# sensor_module_temp_pulse_light_v1.net
KiCad netlist of a schematic drawn in EAGLE
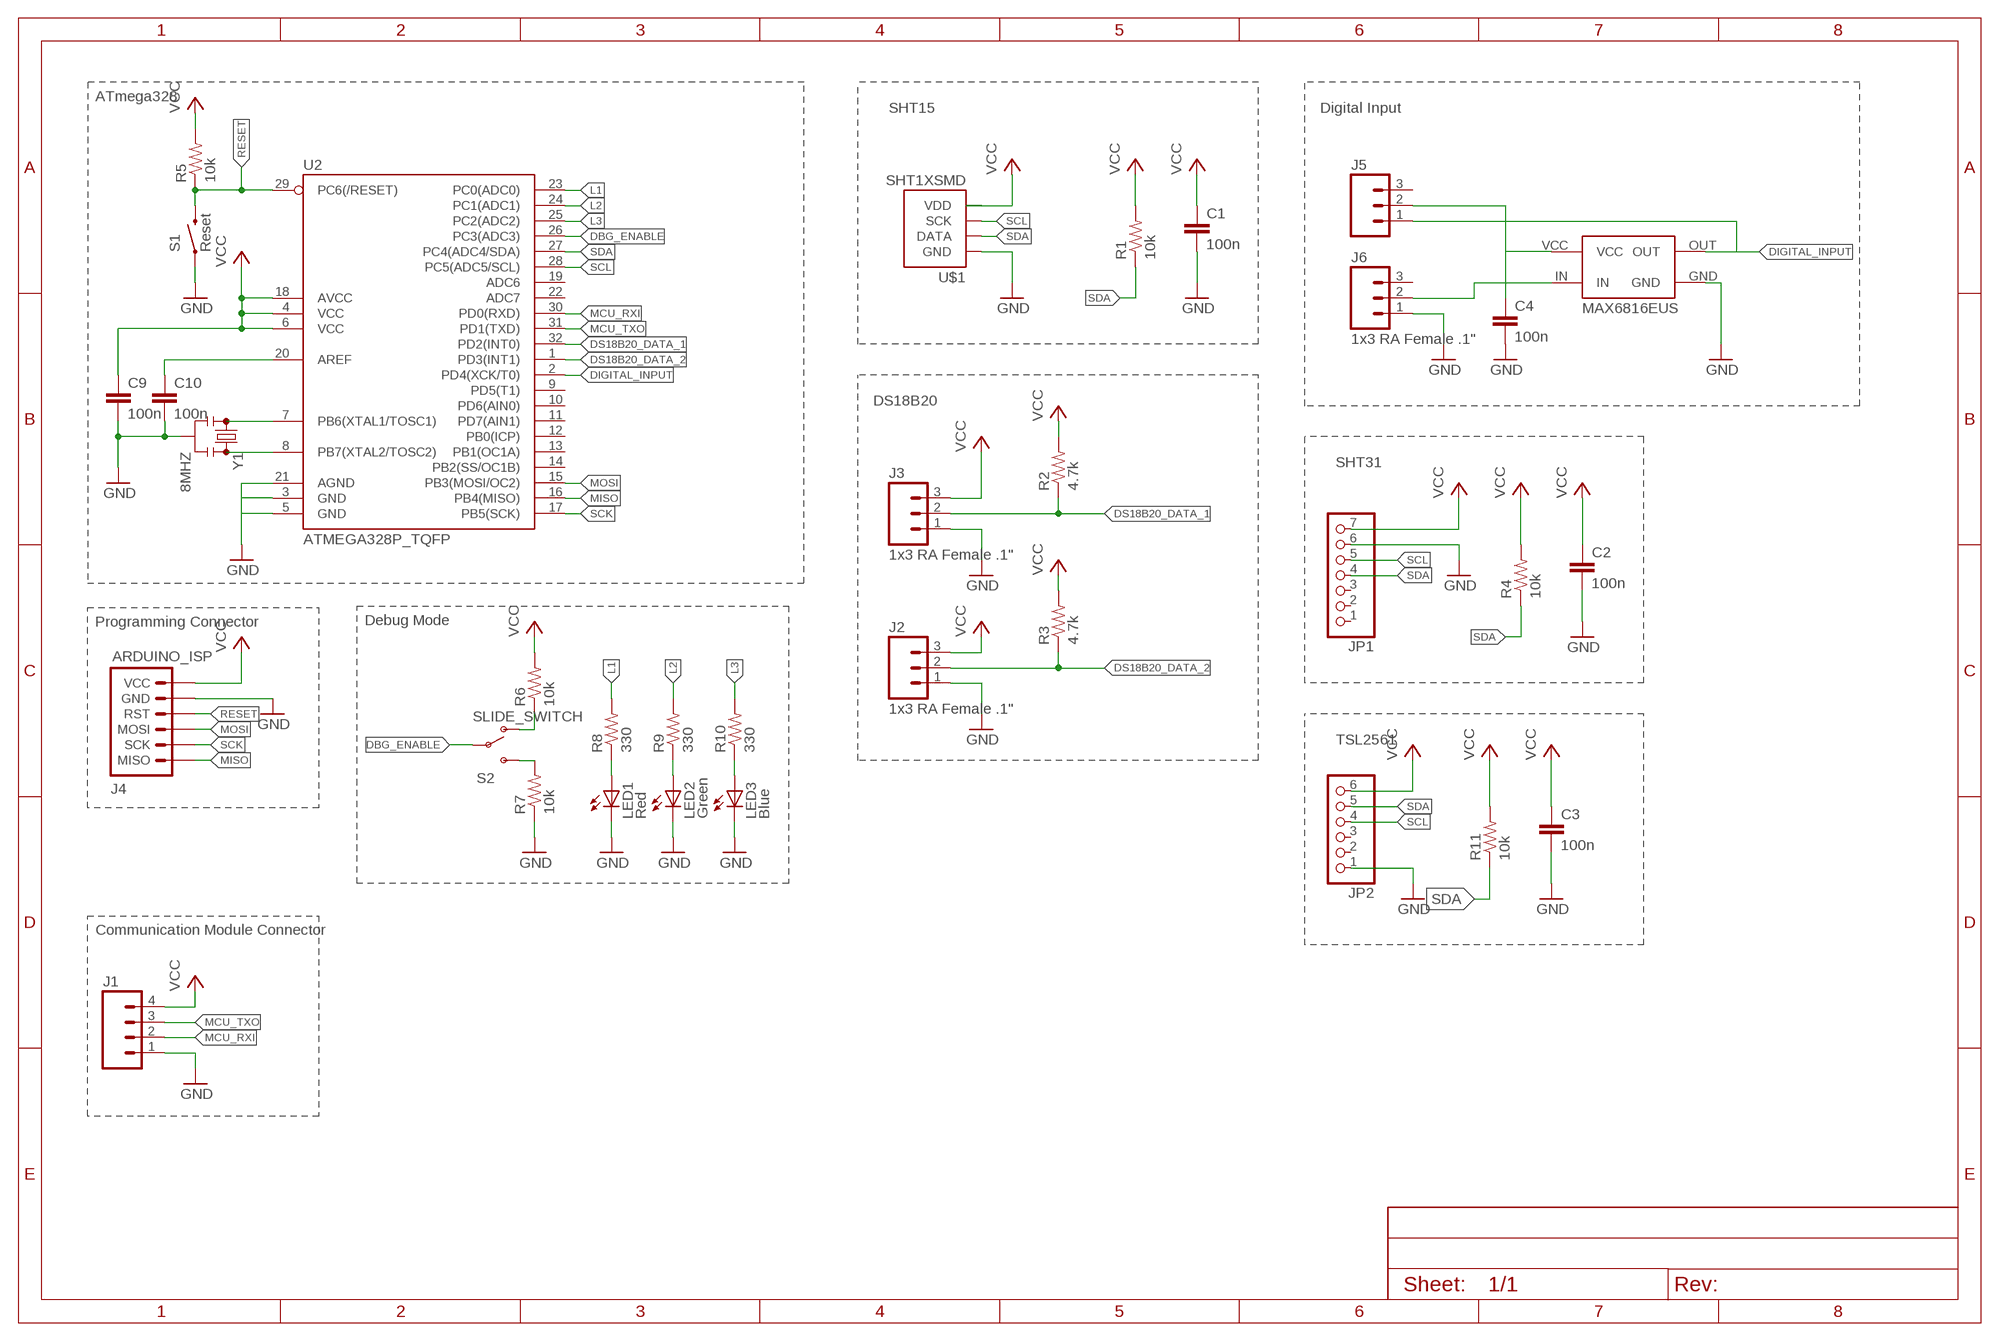
[diagram p0: schematic, sheet 1]

(export (version "E")
  (design (tool "Eeschema 10.0.6"))
  (components
    (comp (ref "C1")
      (value "100n")
      (footprint "eagle-import:C0805")
      (libsource (lib "eagle-import") (part "C"))
    )
    (comp (ref "C2")
      (value "100n")
      (footprint "eagle-import:C0805")
      (libsource (lib "eagle-import") (part "C"))
    )
    (comp (ref "C3")
      (value "100n")
      (footprint "eagle-import:C0805")
      (libsource (lib "eagle-import") (part "C"))
    )
    (comp (ref "C4")
      (value "100n")
      (footprint "eagle-import:C0805")
      (libsource (lib "eagle-import") (part "C"))
    )
    (comp (ref "C9")
      (value "100n")
      (footprint "eagle-import:C0805")
      (libsource (lib "eagle-import") (part "C"))
    )
    (comp (ref "C10")
      (value "100n")
      (footprint "eagle-import:C0805")
      (libsource (lib "eagle-import") (part "C"))
    )
    (comp (ref "J1")
      (value "M041X04_NO_SILK")
      (footprint "eagle-import:1X04_NO_SILK")
      (libsource (lib "eagle-import") (part "M041X04_NO_SILK"))
    )
    (comp (ref "J2")
      (value "1x3 RA Female .1\"")
      (footprint "eagle-import:1X03_SMD_RA_FEMALE")
      (libsource (lib "eagle-import") (part "M03SMD_RA_FEMALE"))
    )
    (comp (ref "J3")
      (value "1x3 RA Female .1\"")
      (footprint "eagle-import:1X03_SMD_RA_FEMALE")
      (libsource (lib "eagle-import") (part "M03SMD_RA_FEMALE"))
    )
    (comp (ref "J4")
      (value "ARDUINO_ISP")
      (footprint "eagle-import:M-2X3")
      (libsource (lib "eagle-import") (part "ARDUINO_ISP"))
    )
    (comp (ref "J5")
      (value "M031X03_NO_SILK")
      (footprint "eagle-import:1X03_NO_SILK")
      (libsource (lib "eagle-import") (part "M031X03_NO_SILK"))
    )
    (comp (ref "J6")
      (value "1x3 RA Female .1\"")
      (footprint "eagle-import:1X03_SMD_RA_FEMALE")
      (libsource (lib "eagle-import") (part "M03SMD_RA_FEMALE"))
    )
    (comp (ref "JP1")
      (value "PINHD-1X7")
      (footprint "eagle-import:1X07")
      (libsource (lib "eagle-import") (part "PINHD-1X7"))
    )
    (comp (ref "JP2")
      (value "PINHD-1X6")
      (footprint "eagle-import:1X06")
      (libsource (lib "eagle-import") (part "PINHD-1X6"))
    )
    (comp (ref "LED1")
      (value "Red")
      (footprint "eagle-import:SML0805")
      (libsource (lib "eagle-import") (part "LEDSML0805"))
    )
    (comp (ref "LED2")
      (value "Green")
      (footprint "eagle-import:SML0805")
      (libsource (lib "eagle-import") (part "LEDSML0805"))
    )
    (comp (ref "LED3")
      (value "Blue")
      (footprint "eagle-import:SML0805")
      (libsource (lib "eagle-import") (part "LEDSML0805"))
    )
    (comp (ref "R1")
      (value "10k")
      (footprint "eagle-import:0805")
      (libsource (lib "eagle-import") (part "RESISTOR0805-RES"))
    )
    (comp (ref "R2")
      (value "4.7k")
      (footprint "eagle-import:0805")
      (libsource (lib "eagle-import") (part "RESISTOR0805-RES"))
    )
    (comp (ref "R3")
      (value "4.7k")
      (footprint "eagle-import:0805")
      (libsource (lib "eagle-import") (part "RESISTOR0805-RES"))
    )
    (comp (ref "R4")
      (value "10k")
      (footprint "eagle-import:0805")
      (libsource (lib "eagle-import") (part "RESISTOR0805-RES"))
    )
    (comp (ref "R5")
      (value "10k")
      (footprint "eagle-import:0805")
      (libsource (lib "eagle-import") (part "RESISTOR0805-RES"))
    )
    (comp (ref "R6")
      (value "10k")
      (footprint "eagle-import:0805")
      (libsource (lib "eagle-import") (part "RESISTOR0805-RES"))
    )
    (comp (ref "R7")
      (value "10k")
      (footprint "eagle-import:0805")
      (libsource (lib "eagle-import") (part "RESISTOR0805-RES"))
    )
    (comp (ref "R8")
      (value "330")
      (footprint "eagle-import:0805")
      (libsource (lib "eagle-import") (part "RESISTOR0805-RES"))
    )
    (comp (ref "R9")
      (value "330")
      (footprint "eagle-import:0805")
      (libsource (lib "eagle-import") (part "RESISTOR0805-RES"))
    )
    (comp (ref "R10")
      (value "330")
      (footprint "eagle-import:0805")
      (libsource (lib "eagle-import") (part "RESISTOR0805-RES"))
    )
    (comp (ref "R11")
      (value "10k")
      (footprint "eagle-import:0805")
      (libsource (lib "eagle-import") (part "RESISTOR0805-RES"))
    )
    (comp (ref "S1")
      (value "Reset")
      (footprint "eagle-import:M-PUSHBUTTON-SMD")
      (libsource (lib "eagle-import") (part "PUSHBUTTON"))
    )
    (comp (ref "S2")
      (value "SLIDE_SWITCH")
      (footprint "eagle-import:P-JS202011SCQN")
      (libsource (lib "eagle-import") (part "SLIDE_SWITCH"))
    )
    (comp (ref "U$1")
      (value "SHT1XSMD")
      (footprint "eagle-import:SHT1X")
      (libsource (lib "eagle-import") (part "SHT1XSMD"))
    )
    (comp (ref "U$2")
      (value "MAX6816EUS")
      (footprint "eagle-import:SOT143")
      (libsource (lib "eagle-import") (part "MAX6816EUS"))
    )
    (comp (ref "U2")
      (value "ATMEGA328P_TQFP")
      (footprint "eagle-import:TQFP32-08")
      (libsource (lib "eagle-import") (part "ATMEGA328P_TQFP"))
    )
    (comp (ref "Y1")
      (value "8MHZ")
      (footprint "eagle-import:RESONATOR-SMD")
      (libsource (lib "eagle-import") (part "RESONATOR8MHZ"))
    )
  )
  (nets
    (net (code "1") (name "DBG_ENABLE") (class "Default")
      (node (ref "S2") (pin "P$2") (pinfunction "MIDDLE_P$2") (pintype "passive"))
      (node (ref "S2") (pin "P$5") (pinfunction "MIDDLE_P$5") (pintype "passive"))
      (node (ref "U2") (pin "26") (pinfunction "PC3(ADC3)_26") (pintype "bidirectional"))
    )
    (net (code "2") (name "DIGITAL_INPUT") (class "Default")
      (node (ref "J5") (pin "1") (pinfunction "1_1") (pintype "passive"))
      (node (ref "U$2") (pin "OUT") (pinfunction "OUT_OUT") (pintype "output"))
      (node (ref "U2") (pin "2") (pinfunction "PD4(XCK/T0)_2") (pintype "bidirectional"))
    )
    (net (code "3") (name "DS18B20_DATA_1") (class "Default")
      (node (ref "J3") (pin "2") (pinfunction "2_2") (pintype "passive"))
      (node (ref "R2") (pin "1") (pinfunction "1_1") (pintype "passive"))
      (node (ref "U2") (pin "32") (pinfunction "PD2(INT0)_32") (pintype "bidirectional"))
    )
    (net (code "4") (name "DS18B20_DATA_2") (class "Default")
      (node (ref "J2") (pin "2") (pinfunction "2_2") (pintype "passive"))
      (node (ref "R3") (pin "1") (pinfunction "1_1") (pintype "passive"))
      (node (ref "U2") (pin "1") (pinfunction "PD3(INT1)_1") (pintype "bidirectional"))
    )
    (net (code "5") (name "GND") (class "Default")
      (node (ref "C1") (pin "2") (pinfunction "2_2") (pintype "passive"))
      (node (ref "C10") (pin "2") (pinfunction "2_2") (pintype "passive"))
      (node (ref "C2") (pin "2") (pinfunction "2_2") (pintype "passive"))
      (node (ref "C3") (pin "2") (pinfunction "2_2") (pintype "passive"))
      (node (ref "C4") (pin "2") (pinfunction "2_2") (pintype "passive"))
      (node (ref "C9") (pin "2") (pinfunction "2_2") (pintype "passive"))
      (node (ref "J1") (pin "1") (pinfunction "1_1") (pintype "passive"))
      (node (ref "J2") (pin "1") (pinfunction "1_1") (pintype "passive"))
      (node (ref "J3") (pin "1") (pinfunction "1_1") (pintype "passive"))
      (node (ref "J4") (pin "P$5") (pinfunction "GND_P$5") (pintype "passive"))
      (node (ref "J6") (pin "1") (pinfunction "1_1") (pintype "passive"))
      (node (ref "JP1") (pin "6") (pinfunction "6_6") (pintype "passive"))
      (node (ref "JP2") (pin "1") (pinfunction "1_1") (pintype "passive"))
      (node (ref "LED1") (pin "C") (pinfunction "C_C") (pintype "passive"))
      (node (ref "LED2") (pin "C") (pinfunction "C_C") (pintype "passive"))
      (node (ref "LED3") (pin "C") (pinfunction "C_C") (pintype "passive"))
      (node (ref "R7") (pin "1") (pinfunction "1_1") (pintype "passive"))
      (node (ref "S1") (pin "1") (pinfunction "LEFT_1") (pintype "passive"))
      (node (ref "S1") (pin "2") (pinfunction "LEFT_2") (pintype "passive"))
      (node (ref "U$1") (pin "1") (pinfunction "GND_1") (pintype "power_in"))
      (node (ref "U$2") (pin "GND") (pinfunction "GND_GND") (pintype "power_in"))
      (node (ref "U2") (pin "21") (pinfunction "AGND_21") (pintype "bidirectional"))
      (node (ref "U2") (pin "3") (pinfunction "GND_3") (pintype "bidirectional"))
      (node (ref "U2") (pin "5") (pinfunction "GND_5") (pintype "bidirectional"))
      (node (ref "Y1") (pin "2") (pinfunction "2_2") (pintype "passive"))
    )
    (net (code "6") (name "L1") (class "Default")
      (node (ref "R8") (pin "2") (pinfunction "2_2") (pintype "passive"))
      (node (ref "U2") (pin "23") (pinfunction "PC0(ADC0)_23") (pintype "bidirectional"))
    )
    (net (code "7") (name "L2") (class "Default")
      (node (ref "R9") (pin "2") (pinfunction "2_2") (pintype "passive"))
      (node (ref "U2") (pin "24") (pinfunction "PC1(ADC1)_24") (pintype "bidirectional"))
    )
    (net (code "8") (name "L3") (class "Default")
      (node (ref "R10") (pin "2") (pinfunction "2_2") (pintype "passive"))
      (node (ref "U2") (pin "25") (pinfunction "PC2(ADC2)_25") (pintype "bidirectional"))
    )
    (net (code "9") (name "MCU_RXI") (class "Default")
      (node (ref "J1") (pin "2") (pinfunction "2_2") (pintype "passive"))
      (node (ref "U2") (pin "30") (pinfunction "PD0(RXD)_30") (pintype "bidirectional"))
    )
    (net (code "10") (name "MCU_TXO") (class "Default")
      (node (ref "J1") (pin "3") (pinfunction "3_3") (pintype "passive"))
      (node (ref "U2") (pin "31") (pinfunction "PD1(TXD)_31") (pintype "bidirectional"))
    )
    (net (code "11") (name "MISO") (class "Default")
      (node (ref "J4") (pin "P$1") (pinfunction "MISO_P$1") (pintype "passive"))
      (node (ref "U2") (pin "16") (pinfunction "PB4(MISO)_16") (pintype "bidirectional"))
    )
    (net (code "12") (name "MOSI") (class "Default")
      (node (ref "J4") (pin "P$3") (pinfunction "MOSI_P$3") (pintype "passive"))
      (node (ref "U2") (pin "15") (pinfunction "PB3(MOSI/OC2)_15") (pintype "bidirectional"))
    )
    (net (code "13") (name "Net-(C4-Pad1)") (class "Default")
      (node (ref "C4") (pin "1") (pinfunction "1_1") (pintype "passive"))
      (node (ref "J5") (pin "2") (pinfunction "2_2") (pintype "passive"))
      (node (ref "U$2") (pin "VCC") (pinfunction "VCC_VCC") (pintype "power_in"))
    )
    (net (code "14") (name "Net-(J6-Pad2)") (class "Default")
      (node (ref "J6") (pin "2") (pinfunction "2_2") (pintype "passive"))
      (node (ref "U$2") (pin "IN") (pinfunction "IN_IN") (pintype "input"))
    )
    (net (code "15") (name "Net-(LED1-PadA)") (class "Default")
      (node (ref "LED1") (pin "A") (pinfunction "A_A") (pintype "passive"))
      (node (ref "R8") (pin "1") (pinfunction "1_1") (pintype "passive"))
    )
    (net (code "16") (name "Net-(LED2-PadA)") (class "Default")
      (node (ref "LED2") (pin "A") (pinfunction "A_A") (pintype "passive"))
      (node (ref "R9") (pin "1") (pinfunction "1_1") (pintype "passive"))
    )
    (net (code "17") (name "Net-(LED3-PadA)") (class "Default")
      (node (ref "LED3") (pin "A") (pinfunction "A_A") (pintype "passive"))
      (node (ref "R10") (pin "1") (pinfunction "1_1") (pintype "passive"))
    )
    (net (code "18") (name "Net-(R6-Pad1)") (class "Default")
      (node (ref "R6") (pin "1") (pinfunction "1_1") (pintype "passive"))
      (node (ref "S2") (pin "P$3") (pinfunction "UPPER_P$3") (pintype "passive"))
      (node (ref "S2") (pin "P$6") (pinfunction "UPPER_P$6") (pintype "passive"))
    )
    (net (code "19") (name "Net-(R7-Pad2)") (class "Default")
      (node (ref "R7") (pin "2") (pinfunction "2_2") (pintype "passive"))
      (node (ref "S2") (pin "P$1") (pinfunction "LOWER_P$1") (pintype "passive"))
      (node (ref "S2") (pin "P$4") (pinfunction "LOWER_P$4") (pintype "passive"))
    )
    (net (code "20") (name "Net-(U2-AREF)") (class "Default")
      (node (ref "C10") (pin "1") (pinfunction "1_1") (pintype "passive"))
      (node (ref "U2") (pin "20") (pinfunction "AREF_20") (pintype "bidirectional"))
    )
    (net (code "21") (name "Net-(U2-PB6(XTAL1{slash}TOSC1))") (class "Default")
      (node (ref "U2") (pin "7") (pinfunction "PB6(XTAL1/TOSC1)_7") (pintype "bidirectional"))
      (node (ref "Y1") (pin "1") (pinfunction "1_1") (pintype "passive"))
    )
    (net (code "22") (name "Net-(U2-PB7(XTAL2{slash}TOSC2))") (class "Default")
      (node (ref "U2") (pin "8") (pinfunction "PB7(XTAL2/TOSC2)_8") (pintype "bidirectional"))
      (node (ref "Y1") (pin "3") (pinfunction "3_3") (pintype "passive"))
    )
    (net (code "23") (name "RESET") (class "Default")
      (node (ref "J4") (pin "P$4") (pinfunction "RST_P$4") (pintype "passive"))
      (node (ref "R5") (pin "1") (pinfunction "1_1") (pintype "passive"))
      (node (ref "S1") (pin "3") (pinfunction "RIGHT_3") (pintype "passive"))
      (node (ref "S1") (pin "4") (pinfunction "RIGHT_4") (pintype "passive"))
      (node (ref "U2") (pin "29") (pinfunction "PC6(/RESET)_29") (pintype "bidirectional"))
    )
    (net (code "24") (name "SCK") (class "Default")
      (node (ref "J4") (pin "P$2") (pinfunction "SCK_P$2") (pintype "passive"))
      (node (ref "U2") (pin "17") (pinfunction "PB5(SCK)_17") (pintype "bidirectional"))
    )
    (net (code "25") (name "SCL") (class "Default")
      (node (ref "JP1") (pin "5") (pinfunction "5_5") (pintype "passive"))
      (node (ref "JP2") (pin "4") (pinfunction "4_4") (pintype "passive"))
      (node (ref "U$1") (pin "3") (pinfunction "SCK_3") (pintype "input"))
      (node (ref "U2") (pin "28") (pinfunction "PC5(ADC5/SCL)_28") (pintype "bidirectional"))
    )
    (net (code "26") (name "SDA") (class "Default")
      (node (ref "JP1") (pin "4") (pinfunction "4_4") (pintype "passive"))
      (node (ref "JP2") (pin "5") (pinfunction "5_5") (pintype "passive"))
      (node (ref "R1") (pin "1") (pinfunction "1_1") (pintype "passive"))
      (node (ref "R11") (pin "1") (pinfunction "1_1") (pintype "passive"))
      (node (ref "R4") (pin "1") (pinfunction "1_1") (pintype "passive"))
      (node (ref "U$1") (pin "2") (pinfunction "DATA_2") (pintype "bidirectional"))
      (node (ref "U2") (pin "27") (pinfunction "PC4(ADC4/SDA)_27") (pintype "bidirectional"))
    )
    (net (code "27") (name "VCC") (class "Default")
      (node (ref "C1") (pin "1") (pinfunction "1_1") (pintype "passive"))
      (node (ref "C2") (pin "1") (pinfunction "1_1") (pintype "passive"))
      (node (ref "C3") (pin "1") (pinfunction "1_1") (pintype "passive"))
      (node (ref "C9") (pin "1") (pinfunction "1_1") (pintype "passive"))
      (node (ref "J1") (pin "4") (pinfunction "4_4") (pintype "passive"))
      (node (ref "J2") (pin "3") (pinfunction "3_3") (pintype "passive"))
      (node (ref "J3") (pin "3") (pinfunction "3_3") (pintype "passive"))
      (node (ref "J4") (pin "P$6") (pinfunction "VCC_P$6") (pintype "passive"))
      (node (ref "JP1") (pin "7") (pinfunction "7_7") (pintype "passive"))
      (node (ref "JP2") (pin "6") (pinfunction "6_6") (pintype "passive"))
      (node (ref "R1") (pin "2") (pinfunction "2_2") (pintype "passive"))
      (node (ref "R11") (pin "2") (pinfunction "2_2") (pintype "passive"))
      (node (ref "R2") (pin "2") (pinfunction "2_2") (pintype "passive"))
      (node (ref "R3") (pin "2") (pinfunction "2_2") (pintype "passive"))
      (node (ref "R4") (pin "2") (pinfunction "2_2") (pintype "passive"))
      (node (ref "R5") (pin "2") (pinfunction "2_2") (pintype "passive"))
      (node (ref "R6") (pin "2") (pinfunction "2_2") (pintype "passive"))
      (node (ref "U$1") (pin "4") (pinfunction "VDD_4") (pintype "power_in"))
      (node (ref "U2") (pin "18") (pinfunction "AVCC_18") (pintype "bidirectional"))
      (node (ref "U2") (pin "4") (pinfunction "VCC_4") (pintype "bidirectional"))
      (node (ref "U2") (pin "6") (pinfunction "VCC_6") (pintype "bidirectional"))
    )
    (net (code "28") (name "unconnected-(J5-Pad3)") (class "Default")
      (node (ref "J5") (pin "3") (pinfunction "3_3") (pintype "passive"))
    )
    (net (code "29") (name "unconnected-(J6-Pad3)") (class "Default")
      (node (ref "J6") (pin "3") (pinfunction "3_3") (pintype "passive"))
    )
    (net (code "30") (name "unconnected-(JP1-Pad1)") (class "Default")
      (node (ref "JP1") (pin "1") (pinfunction "1_1") (pintype "passive"))
    )
    (net (code "31") (name "unconnected-(JP1-Pad2)") (class "Default")
      (node (ref "JP1") (pin "2") (pinfunction "2_2") (pintype "passive"))
    )
    (net (code "32") (name "unconnected-(JP1-Pad3)") (class "Default")
      (node (ref "JP1") (pin "3") (pinfunction "3_3") (pintype "passive"))
    )
    (net (code "33") (name "unconnected-(JP2-Pad2)") (class "Default")
      (node (ref "JP2") (pin "2") (pinfunction "2_2") (pintype "passive"))
    )
    (net (code "34") (name "unconnected-(JP2-Pad3)") (class "Default")
      (node (ref "JP2") (pin "3") (pinfunction "3_3") (pintype "passive"))
    )
    (net (code "35") (name "unconnected-(U2-ADC6-Pad19)") (class "Default")
      (node (ref "U2") (pin "19") (pinfunction "ADC6_19") (pintype "bidirectional"))
    )
    (net (code "36") (name "unconnected-(U2-ADC7-Pad22)") (class "Default")
      (node (ref "U2") (pin "22") (pinfunction "ADC7_22") (pintype "bidirectional"))
    )
    (net (code "37") (name "unconnected-(U2-PB0(ICP)-Pad12)") (class "Default")
      (node (ref "U2") (pin "12") (pinfunction "PB0(ICP)_12") (pintype "bidirectional"))
    )
    (net (code "38") (name "unconnected-(U2-PB1(OC1A)-Pad13)") (class "Default")
      (node (ref "U2") (pin "13") (pinfunction "PB1(OC1A)_13") (pintype "bidirectional"))
    )
    (net (code "39") (name "unconnected-(U2-PB2(SS{slash}OC1B)-Pad14)") (class "Default")
      (node (ref "U2") (pin "14") (pinfunction "PB2(SS/OC1B)_14") (pintype "bidirectional"))
    )
    (net (code "40") (name "unconnected-(U2-PD5(T1)-Pad9)") (class "Default")
      (node (ref "U2") (pin "9") (pinfunction "PD5(T1)_9") (pintype "bidirectional"))
    )
    (net (code "41") (name "unconnected-(U2-PD6(AIN0)-Pad10)") (class "Default")
      (node (ref "U2") (pin "10") (pinfunction "PD6(AIN0)_10") (pintype "bidirectional"))
    )
    (net (code "42") (name "unconnected-(U2-PD7(AIN1)-Pad11)") (class "Default")
      (node (ref "U2") (pin "11") (pinfunction "PD7(AIN1)_11") (pintype "bidirectional"))
    )
  )
)
